# mcu.net
KiCad netlist of a schematic drawn in Altium Designer
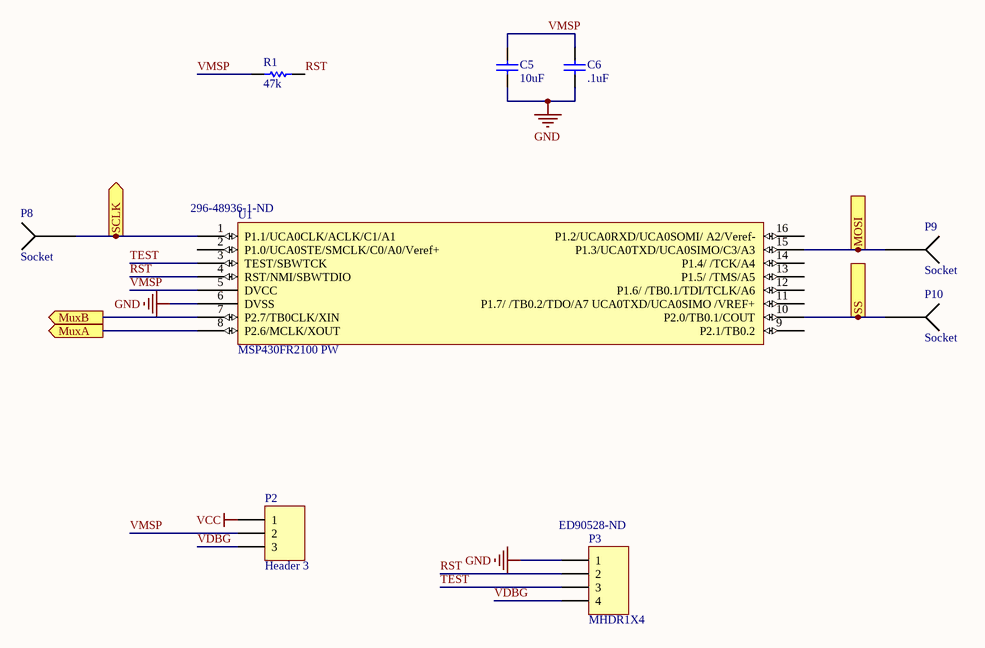
[diagram p0: mcu.SchDoc]

(export (version "E")
  (design (tool "Eeschema 10.0.6"))
  (components
    (comp (ref "C5")
      (value "10uF")
      (footprint "0603")
      (description "Ceramic Capacitor (Surface Mount)")
      (fields (field (name "MANUFACTURER") "Generic Ceramic Chip Cap (TBD)") (field (name "Comment") "Cap"))
      (libsource (lib "maglib") (part "Cap"))
    )
    (comp (ref "C6")
      (value ".1uF")
      (footprint "0603")
      (description "Ceramic Capacitor (Surface Mount)")
      (fields (field (name "MANUFACTURER") "Generic Ceramic Chip Cap (TBD)") (field (name "Comment") "Cap"))
      (libsource (lib "maglib") (part "Cap"))
    )
    (comp (ref "P2")
      (value "Header 3")
      (footprint "HDR1X3")
      (description "Header, 3-Pin")
      (fields (field (name "PUBLISHER") "Altium Limited"))
      (libsource (lib "Miscellaneous Connectors") (part "Header 3"))
    )
    (comp (ref "P3")
      (value "MHDR1X4")
      (footprint "MHDR1X4")
      (description "Header, 4-Pin")
      (fields
        (field (name "SUPPLIER PART NUMBER 1") "ED90528-ND")
        (field (name "PUBLISHER") "Altium Limited")
      )
      (libsource (lib "Miscellaneous Connectors") (part "MHDR1X4"))
    )
    (comp (ref "P8") (value "Socket") (footprint "socket") (libsource (lib "maglib") (part "Socket")))
    (comp (ref "P9") (value "Socket") (footprint "socket") (libsource (lib "maglib") (part "Socket")))
    (comp (ref "P10") (value "Socket") (footprint "socket") (libsource (lib "maglib") (part "Socket")))
    (comp (ref "R1")
      (value "47k")
      (footprint "0603")
      (description "Chip Resistor (Surface Mount)")
      (fields (field (name "MANUFACTURER") "Generic Chip Res (TBD)") (field (name "Comment") "Res"))
      (libsource (lib "maglib") (part "Res"))
    )
    (comp (ref "U1")
      (value "MSP430FR2100 PW")
      (footprint "TSOP65P640X120-16N")
      (fields (field (name "SUPPLIER PART NUMBER 1") "296-48936-1-ND"))
      (libsource (lib "maglib") (part "MSP430FR2100 PW"))
    )
  )
  (nets
    (net (code "1") (name "/MOSI") (class "Default")
      (node (ref "P9") (pin "0") (pinfunction "0_0") (pintype "passive"))
      (node (ref "U1") (pin "15") (pinfunction "P1.3/UCA0TXD/UCA0SIMO/C3/A3_15") (pintype "bidirectional"))
    )
    (net (code "2") (name "/MuxA") (class "Default")
      (node (ref "U1") (pin "8") (pinfunction "P2.6/MCLK/XOUT_8") (pintype "bidirectional"))
    )
    (net (code "3") (name "/MuxB") (class "Default")
      (node (ref "U1") (pin "7") (pinfunction "P2.7/TB0CLK/XIN_7") (pintype "bidirectional"))
    )
    (net (code "4") (name "/RST") (class "Default")
      (node (ref "P3") (pin "2") (pinfunction "2_2") (pintype "passive"))
      (node (ref "R1") (pin "2") (pinfunction "2_2") (pintype "passive"))
      (node (ref "U1") (pin "4") (pinfunction "RST/NMI/SBWTDIO_4") (pintype "bidirectional"))
    )
    (net (code "5") (name "/SCLK") (class "Default")
      (node (ref "P8") (pin "0") (pinfunction "0_0") (pintype "passive"))
      (node (ref "U1") (pin "1") (pinfunction "P1.1/UCA0CLK/ACLK/C1/A1_1") (pintype "bidirectional"))
    )
    (net (code "6") (name "/SS") (class "Default")
      (node (ref "P10") (pin "0") (pinfunction "0_0") (pintype "passive"))
      (node (ref "U1") (pin "10") (pinfunction "P2.0/TB0.1/COUT_10") (pintype "bidirectional"))
    )
    (net (code "7") (name "/TEST") (class "Default")
      (node (ref "P3") (pin "3") (pinfunction "3_3") (pintype "passive"))
      (node (ref "U1") (pin "3") (pinfunction "TEST/SBWTCK_3") (pintype "bidirectional"))
    )
    (net (code "8") (name "/VDBG") (class "Default")
      (node (ref "P2") (pin "3") (pinfunction "3_3") (pintype "passive"))
      (node (ref "P3") (pin "4") (pinfunction "4_4") (pintype "passive"))
    )
    (net (code "9") (name "/VMSP") (class "Default")
      (node (ref "C5") (pin "2") (pinfunction "2_2") (pintype "passive"))
      (node (ref "C6") (pin "2") (pinfunction "2_2") (pintype "passive"))
      (node (ref "P2") (pin "2") (pinfunction "2_2") (pintype "passive"))
      (node (ref "R1") (pin "1") (pinfunction "1_1") (pintype "passive"))
      (node (ref "U1") (pin "5") (pinfunction "DVCC_5") (pintype "power_in"))
    )
    (net (code "10") (name "GND") (class "Default")
      (node (ref "C5") (pin "1") (pinfunction "1_1") (pintype "passive"))
      (node (ref "C6") (pin "1") (pinfunction "1_1") (pintype "passive"))
      (node (ref "P3") (pin "1") (pinfunction "1_1") (pintype "passive"))
      (node (ref "U1") (pin "6") (pinfunction "DVSS_6") (pintype "power_in"))
    )
    (net (code "11") (name "VCC") (class "Default")
      (node (ref "P2") (pin "1") (pinfunction "1_1") (pintype "passive"))
    )
    (net (code "12") (name "unconnected-(U1-P1.0{slash}UCA0STE{slash}SMCLK{slash}C0{slash}A0{slash}Veref+-Pad2)") (class "Default")
      (node (ref "U1") (pin "2") (pinfunction "P1.0/UCA0STE/SMCLK/C0/A0/Veref+_2") (pintype "bidirectional"))
    )
    (net (code "13") (name "unconnected-(U1-P1.2{slash}UCA0RXD{slash}UCA0SOMI{slash}_A2{slash}Veref--Pad16)") (class "Default")
      (node (ref "U1") (pin "16") (pinfunction "P1.2/UCA0RXD/UCA0SOMI/_A2/Veref-_16") (pintype "bidirectional"))
    )
    (net (code "14") (name "unconnected-(U1-P1.4{slash}_{slash}TCK{slash}A4-Pad14)") (class "Default")
      (node (ref "U1") (pin "14") (pinfunction "P1.4/_/TCK/A4_14") (pintype "bidirectional"))
    )
    (net (code "15") (name "unconnected-(U1-P1.5{slash}_{slash}TMS{slash}A5-Pad13)") (class "Default")
      (node (ref "U1") (pin "13") (pinfunction "P1.5/_/TMS/A5_13") (pintype "bidirectional"))
    )
    (net (code "16") (name "unconnected-(U1-P1.6{slash}_{slash}TB0.1{slash}TDI{slash}TCLK{slash}A6-Pad12)") (class "Default")
      (node (ref "U1") (pin "12") (pinfunction "P1.6/_/TB0.1/TDI/TCLK/A6_12") (pintype "bidirectional"))
    )
    (net (code "17") (name "unconnected-(U1-P1.7{slash}_{slash}TB0.2{slash}TDO{slash}A7_UCA0TXD{slash}UCA0SIMO_{slash}VREF+-Pad11)") (class "Default")
      (node (ref "U1") (pin "11") (pinfunction "P1.7/_/TB0.2/TDO/A7_UCA0TXD/UCA0SIMO_/VREF+_11") (pintype "bidirectional"))
    )
    (net (code "18") (name "unconnected-(U1-P2.1{slash}TB0.2-Pad9)") (class "Default")
      (node (ref "U1") (pin "9") (pinfunction "P2.1/TB0.2_9") (pintype "bidirectional"))
    )
  )
)
